# LocoShield-TMH.net
KiCad netlist of a schematic drawn in EAGLE
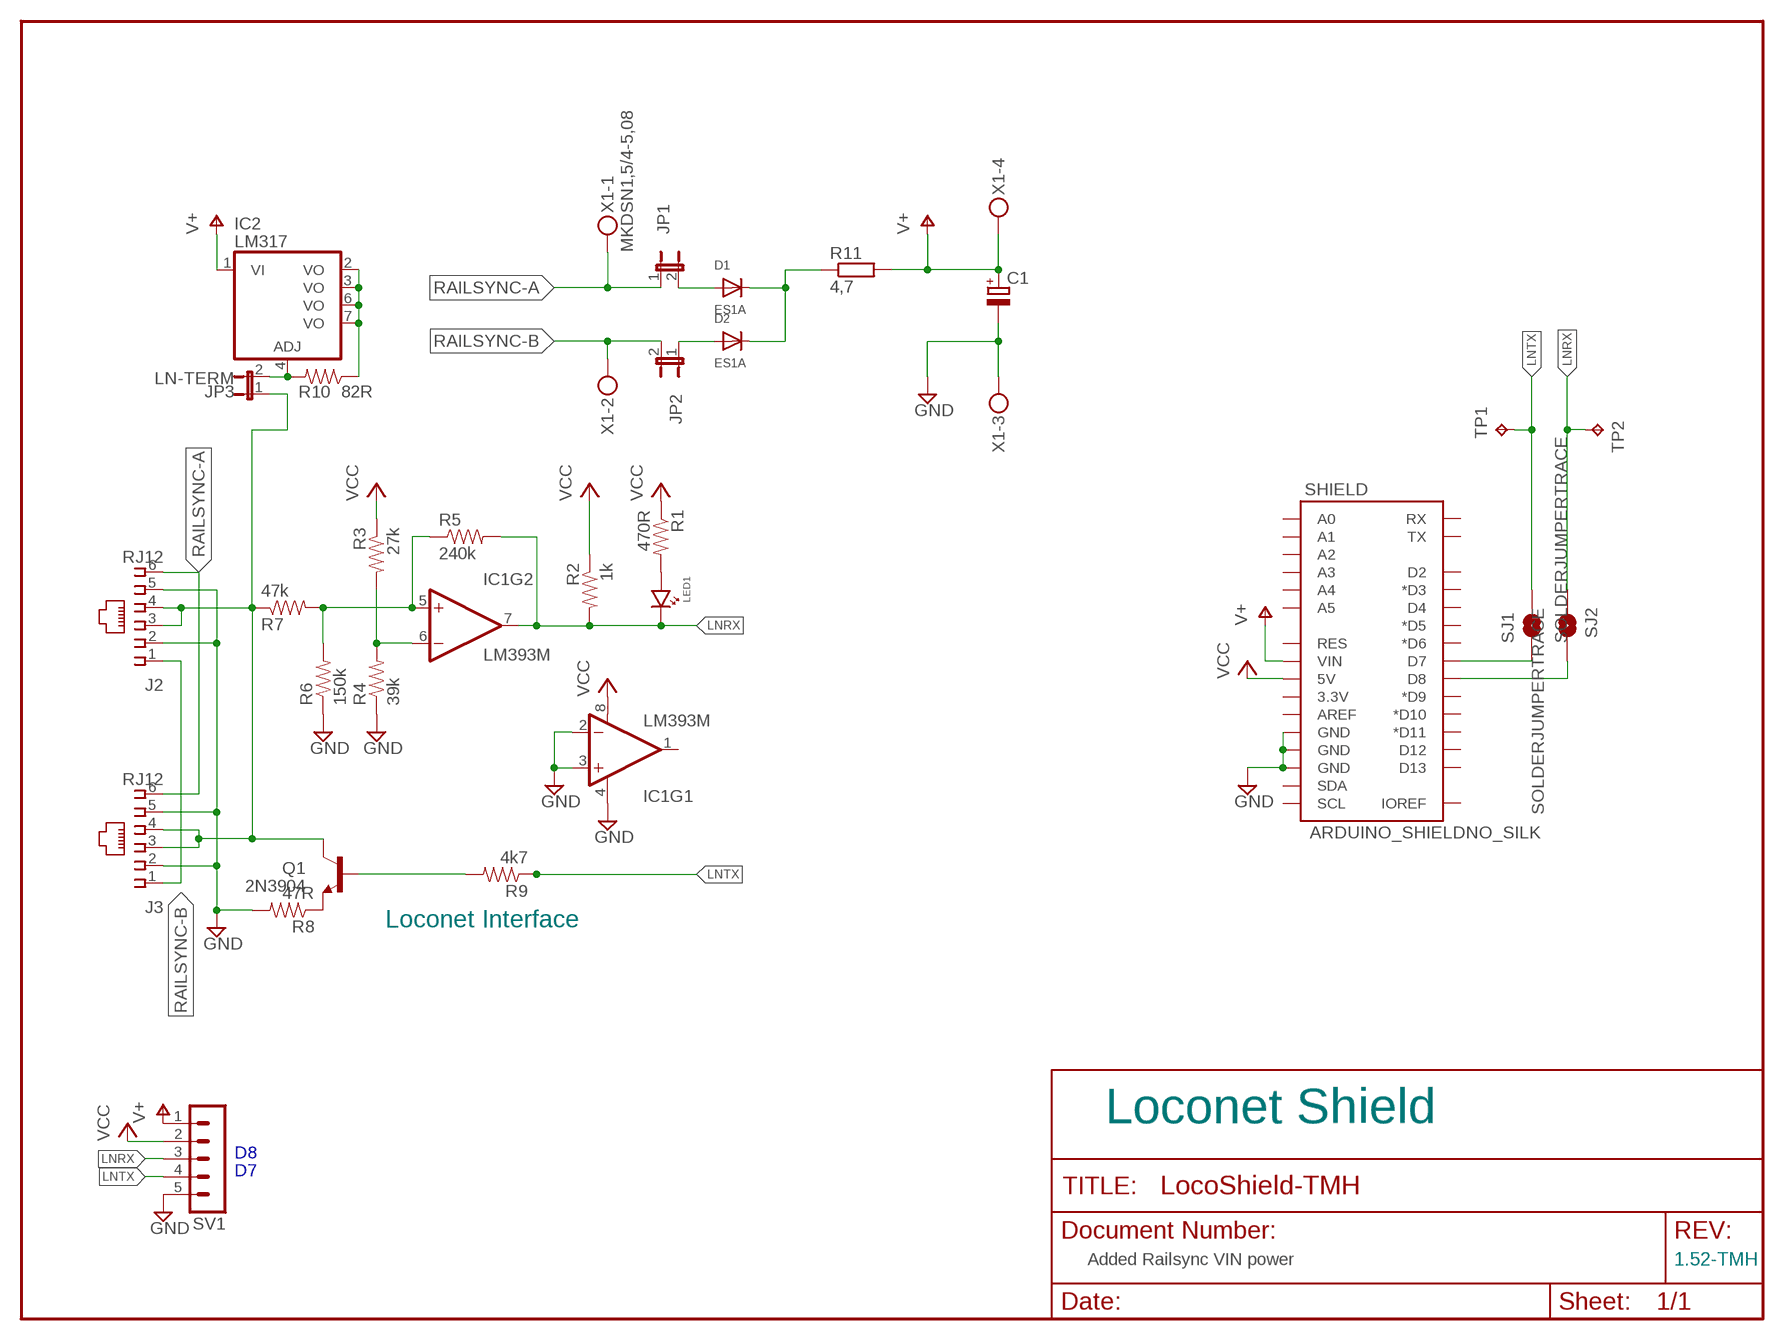
[diagram p0: schematic, sheet 1]

(export (version "E")
  (design (tool "Eeschema 10.0.6"))
  (components
    (comp (ref "C1")
      (value "CPOL-EUE2-5")
      (footprint "eagle-import:E2-5")
      (libsource (lib "eagle-import") (part "CPOL-EUE2-5"))
    )
    (comp (ref "D1")
      (value "ES1A")
      (footprint "eagle-import:SMADIODE")
      (libsource (lib "eagle-import") (part "DIODESMA"))
    )
    (comp (ref "D2")
      (value "ES1A")
      (footprint "eagle-import:SMADIODE")
      (libsource (lib "eagle-import") (part "DIODESMA"))
    )
    (comp (ref "IC1")
      (value "LM393M")
      (footprint "eagle-import:SO08@1")
      (fields (field (name "ELFA") "73-291-96"))
      (libsource (lib "eagle-import") (part "LM393M"))
    )
    (comp (ref "IC2")
      (value "LM317")
      (footprint "eagle-import:SO08")
      (libsource (lib "eagle-import") (part "LM317LD"))
    )
    (comp (ref "J2")
      (value "RJ12")
      (footprint "eagle-import:520250-3")
      (libsource (lib "eagle-import") (part "520250-3"))
    )
    (comp (ref "J3")
      (value "RJ12")
      (footprint "eagle-import:520250-3")
      (libsource (lib "eagle-import") (part "520250-3"))
    )
    (comp (ref "JP1")
      (value "JUMPER-2PTH_LOCK")
      (footprint "eagle-import:1X02_LOCK")
      (libsource (lib "eagle-import") (part "SPCoast_JUMPER-2PTH_LOCK"))
    )
    (comp (ref "JP2")
      (value "JUMPER-2PTH_LOCK")
      (footprint "eagle-import:1X02_LOCK")
      (libsource (lib "eagle-import") (part "SPCoast_JUMPER-2PTH_LOCK"))
    )
    (comp (ref "JP3")
      (value "LN-TERM")
      (footprint "eagle-import:1X02_LOCK")
      (libsource (lib "eagle-import") (part "JUMPER-2PTH_LOCK"))
    )
    (comp (ref "LED1")
      (value "LED0805-LED")
      (footprint "eagle-import:0805-LED")
      (libsource (lib "eagle-import") (part "LED0805-LED"))
    )
    (comp (ref "Q1")
      (value "2N3904")
      (footprint "eagle-import:SOT23-3")
      (libsource (lib "eagle-import") (part "NPN-SOT23-3"))
    )
    (comp (ref "R1")
      (value "470R")
      (footprint "eagle-import:0805-RES")
      (libsource (lib "eagle-import") (part "R0805-RES"))
    )
    (comp (ref "R2")
      (value "1k")
      (footprint "eagle-import:0805-RES")
      (libsource (lib "eagle-import") (part "R0805-RES"))
    )
    (comp (ref "R3")
      (value "27k")
      (footprint "eagle-import:0805-RES")
      (libsource (lib "eagle-import") (part "R0805-RES"))
    )
    (comp (ref "R4")
      (value "39k")
      (footprint "eagle-import:0805-RES")
      (libsource (lib "eagle-import") (part "R0805-RES"))
    )
    (comp (ref "R5")
      (value "240k")
      (footprint "eagle-import:0805-RES")
      (libsource (lib "eagle-import") (part "R0805-RES"))
    )
    (comp (ref "R6")
      (value "150k")
      (footprint "eagle-import:0805-RES")
      (libsource (lib "eagle-import") (part "R0805-RES"))
    )
    (comp (ref "R7")
      (value "47k")
      (footprint "eagle-import:0805-RES")
      (libsource (lib "eagle-import") (part "R0805-RES"))
    )
    (comp (ref "R8")
      (value "47R")
      (footprint "eagle-import:0805-RES")
      (libsource (lib "eagle-import") (part "R0805-RES"))
    )
    (comp (ref "R9")
      (value "4k7")
      (footprint "eagle-import:0805-RES")
      (libsource (lib "eagle-import") (part "R0805-RES"))
    )
    (comp (ref "R10")
      (value "82R")
      (footprint "eagle-import:0805-RES")
      (libsource (lib "eagle-import") (part "R0805-RES"))
    )
    (comp (ref "R11")
      (value "4,7")
      (footprint "eagle-import:R1206")
      (libsource (lib "eagle-import") (part "R-EU_R1206"))
    )
    (comp (ref "SHIELD")
      (value "ARDUINO_SHIELDNO_SILK")
      (footprint "eagle-import:DUEMILANOVE_VIAS")
      (libsource (lib "eagle-import") (part "ARDUINO_SHIELDNO_SILK"))
    )
    (comp (ref "SJ1")
      (value "SOLDERJUMPERTRACE")
      (footprint "eagle-import:SJ_2S-TRACE")
      (libsource (lib "eagle-import") (part "SOLDERJUMPERTRACE"))
    )
    (comp (ref "SJ2")
      (value "SOLDERJUMPERTRACE")
      (footprint "eagle-import:SJ_2S-TRACE")
      (libsource (lib "eagle-import") (part "SOLDERJUMPERTRACE"))
    )
    (comp (ref "SV1")
      (value "MA05-1")
      (footprint "eagle-import:MA05-1")
      (libsource (lib "eagle-import") (part "MA05-1"))
    )
    (comp (ref "TP1")
      (value "TPPAD1-17")
      (footprint "eagle-import:P1-17")
      (libsource (lib "eagle-import") (part "TPPAD1-17"))
    )
    (comp (ref "TP2")
      (value "TPPAD1-17")
      (footprint "eagle-import:P1-17")
      (libsource (lib "eagle-import") (part "TPPAD1-17"))
    )
    (comp (ref "X1")
      (value "MKDSN1,5/4-5,08")
      (footprint "eagle-import:MKDSN1,5_4-5,08")
      (fields (field (name "MPN") "SMKDSN1,5/4-5,08"))
      (libsource (lib "eagle-import") (part "MKDSN1,5/4-5,08"))
    )
  )
  (nets
    (net (code "1") (name "GND") (class "Default")
      (node (ref "C1") (pin "-") (pinfunction "-_-") (pintype "passive"))
      (node (ref "IC1") (pin "2") (pinfunction "-IN_2") (pintype "input"))
      (node (ref "IC1") (pin "3") (pinfunction "+IN_3") (pintype "input"))
      (node (ref "IC1") (pin "4") (pinfunction "V-_4") (pintype "power_in"))
      (node (ref "J2") (pin "2") (pinfunction "2_2") (pintype "passive"))
      (node (ref "J2") (pin "5") (pinfunction "5_5") (pintype "passive"))
      (node (ref "J3") (pin "2") (pinfunction "2_2") (pintype "passive"))
      (node (ref "J3") (pin "5") (pinfunction "5_5") (pintype "passive"))
      (node (ref "R4") (pin "1") (pinfunction "1_1") (pintype "passive"))
      (node (ref "R6") (pin "1") (pinfunction "1_1") (pintype "passive"))
      (node (ref "R8") (pin "2") (pinfunction "2_2") (pintype "passive"))
      (node (ref "SHIELD") (pin "GND@0") (pinfunction "GND_GND@0") (pintype "bidirectional"))
      (node (ref "SHIELD") (pin "GND@1") (pinfunction "GND_GND@1") (pintype "bidirectional"))
      (node (ref "SHIELD") (pin "GND@2") (pinfunction "GND_GND@2") (pintype "bidirectional"))
      (node (ref "SV1") (pin "5") (pinfunction "5_5") (pintype "passive"))
      (node (ref "X1") (pin "3") (pinfunction "KL_3") (pintype "passive"))
    )
    (net (code "2") (name "LNRX") (class "Default")
      (node (ref "IC1") (pin "7") (pinfunction "OUT_7") (pintype "output"))
      (node (ref "LED1") (pin "C") (pinfunction "C_C") (pintype "passive"))
      (node (ref "R2") (pin "2") (pinfunction "2_2") (pintype "passive"))
      (node (ref "R5") (pin "2") (pinfunction "2_2") (pintype "passive"))
      (node (ref "SJ2") (pin "1") (pinfunction "1_1") (pintype "passive"))
      (node (ref "SV1") (pin "3") (pinfunction "3_3") (pintype "passive"))
      (node (ref "TP2") (pin "TP") (pinfunction "TP_TP") (pintype "input"))
    )
    (net (code "3") (name "LNTX") (class "Default")
      (node (ref "R9") (pin "1") (pinfunction "1_1") (pintype "passive"))
      (node (ref "SJ1") (pin "2") (pinfunction "2_2") (pintype "passive"))
      (node (ref "SV1") (pin "4") (pinfunction "4_4") (pintype "passive"))
      (node (ref "TP1") (pin "TP") (pinfunction "TP_TP") (pintype "input"))
    )
    (net (code "4") (name "Net-(D1-PadA)") (class "Default")
      (node (ref "D1") (pin "A") (pinfunction "A_A") (pintype "passive"))
      (node (ref "JP1") (pin "2") (pinfunction "2_2") (pintype "passive"))
    )
    (net (code "5") (name "Net-(D1-PadC)") (class "Default")
      (node (ref "D1") (pin "C") (pinfunction "C_C") (pintype "passive"))
      (node (ref "D2") (pin "C") (pinfunction "C_C") (pintype "passive"))
      (node (ref "R11") (pin "1") (pinfunction "1_1") (pintype "passive"))
    )
    (net (code "6") (name "Net-(D2-PadA)") (class "Default")
      (node (ref "D2") (pin "A") (pinfunction "A_A") (pintype "passive"))
      (node (ref "JP2") (pin "1") (pinfunction "1_1") (pintype "passive"))
    )
    (net (code "7") (name "Net-(IC1B-+IN)") (class "Default")
      (node (ref "IC1") (pin "5") (pinfunction "+IN_5") (pintype "input"))
      (node (ref "R5") (pin "1") (pinfunction "1_1") (pintype "passive"))
      (node (ref "R6") (pin "2") (pinfunction "2_2") (pintype "passive"))
      (node (ref "R7") (pin "2") (pinfunction "2_2") (pintype "passive"))
    )
    (net (code "8") (name "Net-(IC1B--IN)") (class "Default")
      (node (ref "IC1") (pin "6") (pinfunction "-IN_6") (pintype "input"))
      (node (ref "R3") (pin "2") (pinfunction "2_2") (pintype "passive"))
      (node (ref "R4") (pin "2") (pinfunction "2_2") (pintype "passive"))
    )
    (net (code "9") (name "Net-(IC2-ADJ)") (class "Default")
      (node (ref "IC2") (pin "4") (pinfunction "ADJ_4") (pintype "input"))
      (node (ref "JP3") (pin "2") (pinfunction "2_2") (pintype "passive"))
      (node (ref "R10") (pin "2") (pinfunction "2_2") (pintype "passive"))
    )
    (net (code "10") (name "Net-(IC2-VO-Pad2)") (class "Default")
      (node (ref "IC2") (pin "2") (pinfunction "VO_2") (pintype "passive"))
      (node (ref "IC2") (pin "3") (pinfunction "VO_3") (pintype "passive"))
      (node (ref "IC2") (pin "6") (pinfunction "VO_6") (pintype "passive"))
      (node (ref "IC2") (pin "7") (pinfunction "VO_7") (pintype "passive"))
      (node (ref "R10") (pin "1") (pinfunction "1_1") (pintype "passive"))
    )
    (net (code "11") (name "Net-(LED1-PadA)") (class "Default")
      (node (ref "LED1") (pin "A") (pinfunction "A_A") (pintype "passive"))
      (node (ref "R1") (pin "2") (pinfunction "2_2") (pintype "passive"))
    )
    (net (code "12") (name "Net-(Q1-B)") (class "Default")
      (node (ref "Q1") (pin "1") (pinfunction "B_1") (pintype "passive"))
      (node (ref "R9") (pin "2") (pinfunction "2_2") (pintype "passive"))
    )
    (net (code "13") (name "Net-(Q1-C)") (class "Default")
      (node (ref "J2") (pin "3") (pinfunction "3_3") (pintype "passive"))
      (node (ref "J2") (pin "4") (pinfunction "4_4") (pintype "passive"))
      (node (ref "J3") (pin "3") (pinfunction "3_3") (pintype "passive"))
      (node (ref "J3") (pin "4") (pinfunction "4_4") (pintype "passive"))
      (node (ref "JP3") (pin "1") (pinfunction "1_1") (pintype "passive"))
      (node (ref "Q1") (pin "3") (pinfunction "C_3") (pintype "passive"))
      (node (ref "R7") (pin "1") (pinfunction "1_1") (pintype "passive"))
    )
    (net (code "14") (name "Net-(Q1-E)") (class "Default")
      (node (ref "Q1") (pin "2") (pinfunction "E_2") (pintype "passive"))
      (node (ref "R8") (pin "1") (pinfunction "1_1") (pintype "passive"))
    )
    (net (code "15") (name "Net-(SHIELD-PadD7)") (class "Default")
      (node (ref "SHIELD") (pin "D7") (pinfunction "D7_D7") (pintype "bidirectional"))
      (node (ref "SJ1") (pin "1") (pinfunction "1_1") (pintype "passive"))
    )
    (net (code "16") (name "Net-(SHIELD-PadD8)") (class "Default")
      (node (ref "SHIELD") (pin "D8") (pinfunction "D8_D8") (pintype "bidirectional"))
      (node (ref "SJ2") (pin "2") (pinfunction "2_2") (pintype "passive"))
    )
    (net (code "17") (name "RAILSYNC-A") (class "Default")
      (node (ref "J2") (pin "6") (pinfunction "6_6") (pintype "passive"))
      (node (ref "J3") (pin "6") (pinfunction "6_6") (pintype "passive"))
      (node (ref "JP1") (pin "1") (pinfunction "1_1") (pintype "passive"))
      (node (ref "X1") (pin "1") (pinfunction "KL_1") (pintype "passive"))
    )
    (net (code "18") (name "RAILSYNC-B") (class "Default")
      (node (ref "J2") (pin "1") (pinfunction "1_1") (pintype "passive"))
      (node (ref "J3") (pin "1") (pinfunction "1_1") (pintype "passive"))
      (node (ref "JP2") (pin "2") (pinfunction "2_2") (pintype "passive"))
      (node (ref "X1") (pin "2") (pinfunction "KL_2") (pintype "passive"))
    )
    (net (code "19") (name "V+") (class "Default")
      (node (ref "C1") (pin "+") (pinfunction "+_+") (pintype "passive"))
      (node (ref "IC2") (pin "1") (pinfunction "VI_1") (pintype "input"))
      (node (ref "R11") (pin "2") (pinfunction "2_2") (pintype "passive"))
      (node (ref "SHIELD") (pin "VIN") (pinfunction "VIN_VIN") (pintype "bidirectional"))
      (node (ref "SV1") (pin "1") (pinfunction "1_1") (pintype "passive"))
      (node (ref "X1") (pin "4") (pinfunction "KL_4") (pintype "passive"))
    )
    (net (code "20") (name "VCC") (class "Default")
      (node (ref "IC1") (pin "8") (pinfunction "V+_8") (pintype "power_in"))
      (node (ref "R1") (pin "1") (pinfunction "1_1") (pintype "passive"))
      (node (ref "R2") (pin "1") (pinfunction "1_1") (pintype "passive"))
      (node (ref "R3") (pin "1") (pinfunction "1_1") (pintype "passive"))
      (node (ref "SHIELD") (pin "5V") (pinfunction "5V_5V") (pintype "bidirectional"))
      (node (ref "SV1") (pin "2") (pinfunction "2_2") (pintype "passive"))
    )
    (net (code "21") (name "unconnected-(IC1A-OUT-Pad1)") (class "Default")
      (node (ref "IC1") (pin "1") (pinfunction "OUT_1") (pintype "output"))
    )
    (net (code "22") (name "unconnected-(SHIELD-*D3-PadD3)") (class "Default")
      (node (ref "SHIELD") (pin "D3") (pinfunction "*D3_D3") (pintype "bidirectional"))
    )
    (net (code "23") (name "unconnected-(SHIELD-*D5-PadD5)") (class "Default")
      (node (ref "SHIELD") (pin "D5") (pinfunction "*D5_D5") (pintype "bidirectional"))
    )
    (net (code "24") (name "unconnected-(SHIELD-*D6-PadD6)") (class "Default")
      (node (ref "SHIELD") (pin "D6") (pinfunction "*D6_D6") (pintype "bidirectional"))
    )
    (net (code "25") (name "unconnected-(SHIELD-*D9-PadD9)") (class "Default")
      (node (ref "SHIELD") (pin "D9") (pinfunction "*D9_D9") (pintype "bidirectional"))
    )
    (net (code "26") (name "unconnected-(SHIELD-*D10-PadD10)") (class "Default")
      (node (ref "SHIELD") (pin "D10") (pinfunction "*D10_D10") (pintype "bidirectional"))
    )
    (net (code "27") (name "unconnected-(SHIELD-*D11-PadD11)") (class "Default")
      (node (ref "SHIELD") (pin "D11") (pinfunction "*D11_D11") (pintype "bidirectional"))
    )
    (net (code "28") (name "unconnected-(SHIELD-Pad3.3V)") (class "Default")
      (node (ref "SHIELD") (pin "3.3V") (pinfunction "3.3V_3.3V") (pintype "bidirectional"))
    )
    (net (code "29") (name "unconnected-(SHIELD-PadA0)") (class "Default")
      (node (ref "SHIELD") (pin "A0") (pinfunction "A0_A0") (pintype "bidirectional"))
    )
    (net (code "30") (name "unconnected-(SHIELD-PadA1)") (class "Default")
      (node (ref "SHIELD") (pin "A1") (pinfunction "A1_A1") (pintype "bidirectional"))
    )
    (net (code "31") (name "unconnected-(SHIELD-PadA2)") (class "Default")
      (node (ref "SHIELD") (pin "A2") (pinfunction "A2_A2") (pintype "bidirectional"))
    )
    (net (code "32") (name "unconnected-(SHIELD-PadA3)") (class "Default")
      (node (ref "SHIELD") (pin "A3") (pinfunction "A3_A3") (pintype "bidirectional"))
    )
    (net (code "33") (name "unconnected-(SHIELD-PadA4)") (class "Default")
      (node (ref "SHIELD") (pin "A4") (pinfunction "A4_A4") (pintype "bidirectional"))
    )
    (net (code "34") (name "unconnected-(SHIELD-PadA5)") (class "Default")
      (node (ref "SHIELD") (pin "A5") (pinfunction "A5_A5") (pintype "bidirectional"))
    )
    (net (code "35") (name "unconnected-(SHIELD-PadAREF)") (class "Default")
      (node (ref "SHIELD") (pin "AREF") (pinfunction "AREF_AREF") (pintype "bidirectional"))
    )
    (net (code "36") (name "unconnected-(SHIELD-PadD2)") (class "Default")
      (node (ref "SHIELD") (pin "D2") (pinfunction "D2_D2") (pintype "bidirectional"))
    )
    (net (code "37") (name "unconnected-(SHIELD-PadD4)") (class "Default")
      (node (ref "SHIELD") (pin "D4") (pinfunction "D4_D4") (pintype "bidirectional"))
    )
    (net (code "38") (name "unconnected-(SHIELD-PadD12)") (class "Default")
      (node (ref "SHIELD") (pin "D12") (pinfunction "D12_D12") (pintype "bidirectional"))
    )
    (net (code "39") (name "unconnected-(SHIELD-PadD13)") (class "Default")
      (node (ref "SHIELD") (pin "D13") (pinfunction "D13_D13") (pintype "bidirectional"))
    )
    (net (code "40") (name "unconnected-(SHIELD-PadIOREF)") (class "Default")
      (node (ref "SHIELD") (pin "IOREF") (pinfunction "IOREF_IOREF") (pintype "bidirectional"))
    )
    (net (code "41") (name "unconnected-(SHIELD-PadRES)") (class "Default")
      (node (ref "SHIELD") (pin "RES") (pinfunction "RES_RES") (pintype "bidirectional"))
    )
    (net (code "42") (name "unconnected-(SHIELD-PadRX)") (class "Default")
      (node (ref "SHIELD") (pin "RX") (pinfunction "RX_RX") (pintype "bidirectional"))
    )
    (net (code "43") (name "unconnected-(SHIELD-PadSCL)") (class "Default")
      (node (ref "SHIELD") (pin "SCL") (pinfunction "SCL_SCL") (pintype "bidirectional"))
    )
    (net (code "44") (name "unconnected-(SHIELD-PadSDA)") (class "Default")
      (node (ref "SHIELD") (pin "SDA") (pinfunction "SDA_SDA") (pintype "bidirectional"))
    )
    (net (code "45") (name "unconnected-(SHIELD-PadTX)") (class "Default")
      (node (ref "SHIELD") (pin "TX") (pinfunction "TX_TX") (pintype "bidirectional"))
    )
  )
)
